# Power.net
KiCad netlist of a schematic drawn in Altium Designer
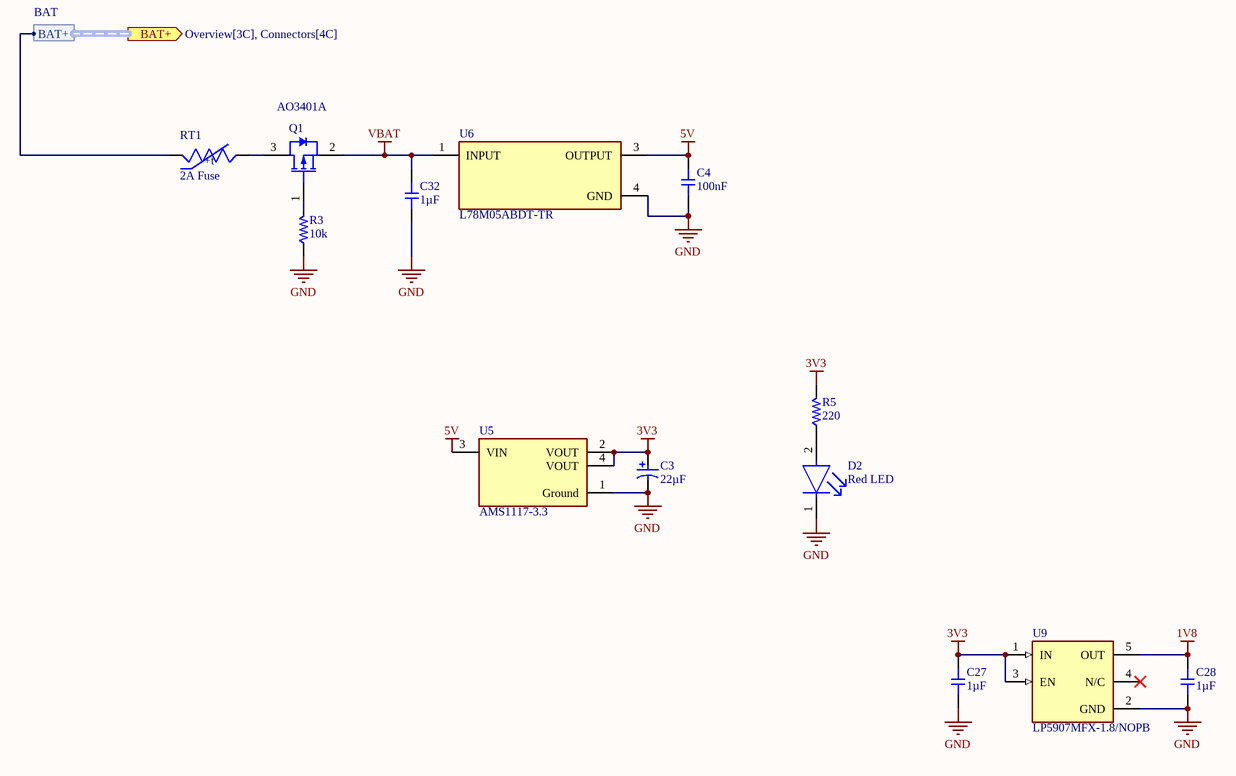
[diagram p0: Power.SchDoc]

(export (version "E")
  (design (tool "Eeschema 10.0.6"))
  (components
    (comp (ref "C3")
      (value "22µF")
      (footprint "KEMT-T491-B_M")
      (fields (field (name "JLCPCB PART NUMBER") "C1953127") (field (name "Comment") "TR3B226K010C0700"))
      (libsource (lib "StrathSEDS") (part "CAP-P-2"))
    )
    (comp (ref "C4")
      (value "100nF")
      (footprint "CAP-0402")
      (description "Capacitor, Ceramic (MLCC), 100nF, ±10%, 16V, X7R, ±10%, SMD 0402")
      (fields (field (name "TOLERANCE") "10%") (field (name "JLCPCB BASIC PART") "Yes"))
      (libsource (lib "StrathSEDS") (part "GRM21BR61H106KE43L"))
    )
    (comp (ref "C27")
      (value "1µF")
      (footprint "CAP-0402")
      (description "Capacitor, Ceramic (MLCC), 1uF, ±10%, 25V, X5R, ±10%, SMD 0402")
      (fields (field (name "TOLERANCE") "10%") (field (name "JLCPCB BASIC PART") "Yes"))
      (libsource (lib "StrathSEDS") (part "GRM21BR61H106KE43L"))
    )
    (comp (ref "C28")
      (value "1µF")
      (footprint "CAP-0402")
      (description "Capacitor, Ceramic (MLCC), 1uF, ±10%, 25V, X5R, ±10%, SMD 0402")
      (fields (field (name "TOLERANCE") "10%") (field (name "JLCPCB BASIC PART") "Yes"))
      (libsource (lib "StrathSEDS") (part "GRM21BR61H106KE43L"))
    )
    (comp (ref "C32")
      (value "1µF")
      (footprint "CAP-0402")
      (description "Capacitor, Ceramic (MLCC), 1uF, ±10%, 25V, X5R, ±10%, SMD 0402")
      (fields (field (name "TOLERANCE") "10%") (field (name "JLCPCB BASIC PART") "Yes"))
      (libsource (lib "StrathSEDS") (part "GRM21BR61H106KE43L"))
    )
    (comp (ref "D2")
      (value "Red LED")
      (footprint "FP-LTST-C190GKT-MFG")
      (description "SZYY0603R")
      (fields (field (name "JLCPCB PART NUMBER") "C2286"))
      (libsource (lib "StrathSEDS Mach 22") (part "8706943c75ba83719d021d2fdc84c58"))
    )
    (comp (ref "Q1")
      (value "AO3401A")
      (footprint "AO-SOT-23-3L_V")
      (description "P沟道 VDS=-30V VGS=±12V ID=-4A P=1.4W")
      (fields (field (name "JLCPCB PART NUMBER") "C15127"))
      (libsource (lib "StrathSEDS Mach 22") (part "PEMOS-GSD-3"))
    )
    (comp (ref "R3")
      (value "10k")
      (footprint "RES-0402")
      (description "Resistor, 10kΩ, ±1%, 62.5mW, 50V, ±100ppm/℃, -55℃~+155℃, SMD 0402")
      (fields (field (name "TOLERANCE") "1%") (field (name "JLCPCB PART NUMBER") "C25744"))
      (libsource (lib "StrathSEDS") (part "1206W4F7500T5E"))
    )
    (comp (ref "R5")
      (value "220")
      (footprint "RES-0402")
      (description "Resistor, 220Ω, ±1%, 62.5mW, 50V, ±100ppm/℃, -55℃~+155℃, SMD 0402")
      (fields (field (name "MANUFACTURER") "Uniroyal") (field (name "TOLERANCE") "1%"))
      (libsource (lib "StrathSEDS") (part "1206W4F7500T5E"))
    )
    (comp (ref "RT1")
      (value "2A Fuse")
      (footprint "THRMC1608X95N")
      (description "PTC Resettable Fuse: 2A Hold, 4A Trip, 0603")
      (fields (field (name "MP") "BSMD0603L-200") (field (name "JLCPCB PART NUMBER") "C2757930"))
      (libsource (lib "StrathSEDS") (part "BSMD0603L-200"))
    )
    (comp (ref "U5")
      (value "AMS1117-3.3")
      (footprint "FP-AMS1117-IPC_B")
      (description "Fixed Positive LDO Regulator, 3.3V, 1.3V Dropout, PDSO3")
      (fields (field (name "JLCPCB PART NUMBER") "C6186"))
      (libsource (lib "StrathSEDS") (part "8bdbb5f8e77002000e30dd2845d0354"))
    )
    (comp (ref "U6")
      (value "L78M05ABDT-TR")
      (footprint "FP-L78M05ABDT-TR-MFG")
      (description "Fixed Positive Standard Regulator, 5VBIPolar, PSSO2")
      (fields (field (name "JLCPCB PART NUMBER") "C58069"))
      (libsource (lib "StrathSEDS") (part "9f44cecb34f7d82ec50de3d0489c717"))
    )
    (comp (ref "U9")
      (value "LP5907MFX-1.8/NOPB")
      (footprint "SOT95P280X145-5N")
      (fields (field (name "JLCPCB PART NUMBER") "C92498"))
      (libsource (lib "StrathSEDS") (part "LP5907MFX-1.8/NOPB"))
    )
  )
  (nets
    (net (code "3") (name "1V8") (class "Default")
      (node (ref "C28") (pin "2") (pinfunction "2_2") (pintype "passive"))
      (node (ref "U9") (pin "5") (pinfunction "OUT_5") (pintype "power_in"))
    )
    (net (code "4") (name "3V3") (class "Default")
      (node (ref "C27") (pin "2") (pinfunction "2_2") (pintype "passive"))
      (node (ref "C3") (pin "1") (pinfunction "1_1") (pintype "passive"))
      (node (ref "R5") (pin "2") (pinfunction "2_2") (pintype "passive"))
      (node (ref "U5") (pin "2") (pinfunction "VOUT_2") (pintype "passive"))
      (node (ref "U5") (pin "4") (pinfunction "VOUT_4") (pintype "passive"))
      (node (ref "U9") (pin "1") (pinfunction "IN_1") (pintype "input"))
      (node (ref "U9") (pin "3") (pinfunction "EN_3") (pintype "input"))
    )
    (net (code "5") (name "5V") (class "Default")
      (node (ref "C4") (pin "2") (pinfunction "2_2") (pintype "passive"))
      (node (ref "U5") (pin "3") (pinfunction "VIN_3") (pintype "power_in"))
      (node (ref "U6") (pin "3") (pinfunction "OUTPUT_3") (pintype "power_in"))
    )
    (net (code "6") (name "GND") (class "Default")
      (node (ref "C27") (pin "1") (pinfunction "1_1") (pintype "passive"))
      (node (ref "C28") (pin "1") (pinfunction "1_1") (pintype "passive"))
      (node (ref "C3") (pin "2") (pinfunction "2_2") (pintype "passive"))
      (node (ref "C32") (pin "1") (pinfunction "1_1") (pintype "passive"))
      (node (ref "C4") (pin "1") (pinfunction "1_1") (pintype "passive"))
      (node (ref "D2") (pin "1") (pinfunction "C_1") (pintype "passive"))
      (node (ref "R3") (pin "1") (pinfunction "1_1") (pintype "passive"))
      (node (ref "U5") (pin "1") (pinfunction "Ground_1") (pintype "power_in"))
      (node (ref "U6") (pin "4") (pinfunction "GND_4") (pintype "power_in"))
      (node (ref "U9") (pin "2") (pinfunction "GND_2") (pintype "power_in"))
    )
    (net (code "7") (name "Net-(D2-A)") (class "Default")
      (node (ref "D2") (pin "2") (pinfunction "A_2") (pintype "passive"))
      (node (ref "R5") (pin "1") (pinfunction "1_1") (pintype "passive"))
    )
    (net (code "8") (name "Net-(Q1-DRAIN)") (class "Default")
      (node (ref "Q1") (pin "3") (pinfunction "DRAIN_3") (pintype "passive"))
      (node (ref "RT1") (pin "2") (pinfunction "2_2") (pintype "passive"))
    )
    (net (code "9") (name "Net-(Q1-GATE)") (class "Default")
      (node (ref "Q1") (pin "1") (pinfunction "GATE_1") (pintype "passive"))
      (node (ref "R3") (pin "2") (pinfunction "2_2") (pintype "passive"))
    )
    (net (code "10") (name "VBAT") (class "Default")
      (node (ref "C32") (pin "2") (pinfunction "2_2") (pintype "passive"))
      (node (ref "Q1") (pin "2") (pinfunction "SOURCE_2") (pintype "passive"))
      (node (ref "U6") (pin "1") (pinfunction "INPUT_1") (pintype "power_in"))
    )
    (net (code "11") (name "unconnected-(RT1-Pad1)") (class "Default")
      (node (ref "RT1") (pin "1") (pinfunction "1_1") (pintype "passive"))
    )
    (net (code "12") (name "unconnected-(U9-N{slash}C-Pad4)") (class "Default")
      (node (ref "U9") (pin "4") (pinfunction "N/C_4") (pintype "passive+no_connect"))
    )
  )
)
